# Hoja_Buck2.net
KiCad netlist of a schematic drawn in Altium Designer
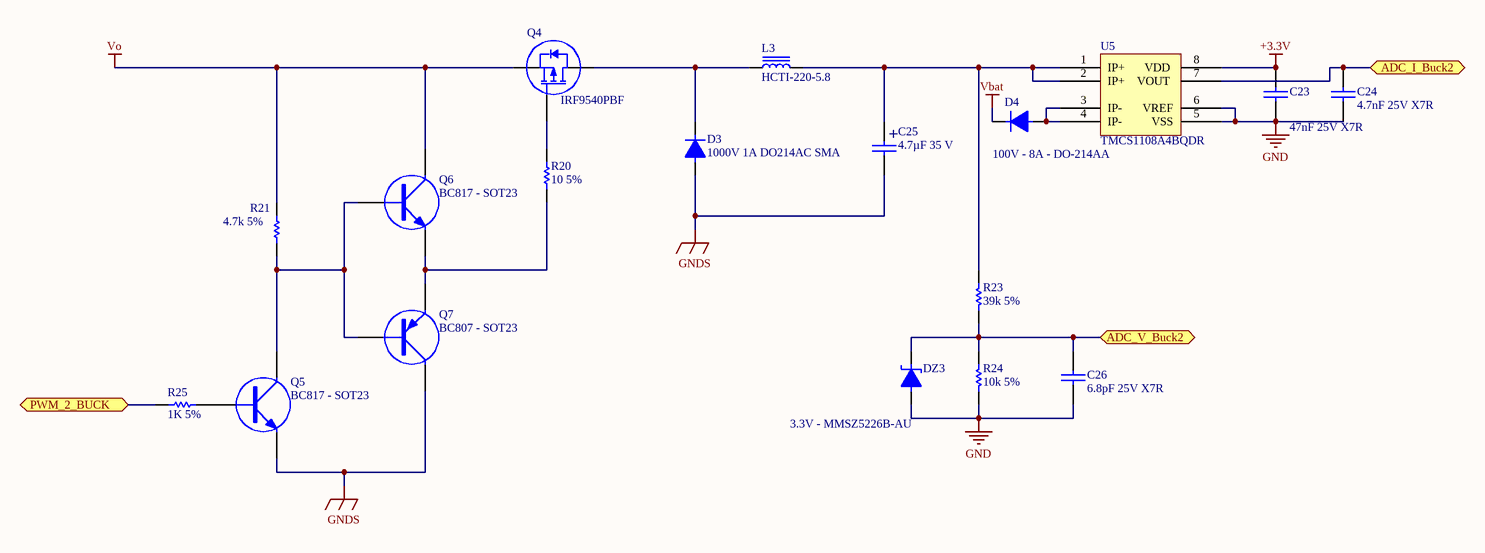
[diagram p0: Hoja_Buck2.SchDoc]

(export (version "E")
  (design (tool "Eeschema 10.0.6"))
  (components
    (comp (ref "C23")
      (value "47nF 25V X7R")
      (footprint "0805")
      (libsource (lib "Libreria_Casera") (part "CAP"))
    )
    (comp (ref "C24")
      (value "4.7nF 25V X7R")
      (footprint "0805")
      (libsource (lib "Libreria_Casera") (part "CAP"))
    )
    (comp (ref "C25")
      (value "4.7µF 35 V")
      (footprint "CAPSMD8x8.3")
      (libsource (lib "Libreria_Casera") (part "CAPPOL"))
    )
    (comp (ref "C26")
      (value "6.8pF 25V X7R")
      (footprint "0805")
      (libsource (lib "Libreria_Casera") (part "CAP"))
    )
    (comp (ref "D3")
      (value "1000V 1A DO214AC SMA")
      (footprint "DO-214AC")
      (description "Diodos Estándar 1000 V 1A Montaje en superficie SMA")
      (libsource (lib "Libreria_Casera") (part "DIODO"))
    )
    (comp (ref "D4")
      (value "100V - 8A - DO-214AA")
      (footprint "SMPA-DIODE")
      (libsource (lib "Libreria_Casera") (part "DIODO"))
    )
    (comp (ref "DZ3")
      (value "3.3V - MMSZ5226B-AU")
      (footprint "sod123")
      (libsource (lib "Libreria_Casera") (part "DIODO ZENER"))
    )
    (comp (ref "L3")
      (value "HCTI-220-5.8")
      (footprint "IND_HCTI-220-5.8:IND_HCTI-220-5.8")
      (description "https://ar.mouser.com/datasheet/2/643/ds-st-high-current-torodial-inductors-series-1661536.pdf")
      (libsource (lib "Libreria_Casera") (part "INDUCTOR"))
    )
    (comp (ref "Q4")
      (value "IRF9540PBF")
      (footprint "TO-220 V")
      (libsource (lib "Libreria_Casera") (part "MOSFET P"))
    )
    (comp (ref "Q5")
      (value "BC817 - SOT23")
      (footprint "SOT23-3")
      (description "45V NPN SMALL SIGNAL TRANSISTOR IN SOT23")
      (libsource (lib "Libreria_Casera") (part "TRANSISTOR NPN"))
    )
    (comp (ref "Q6")
      (value "BC817 - SOT23")
      (footprint "SOT23-3")
      (description "45V NPN SMALL SIGNAL TRANSISTOR IN SOT23")
      (libsource (lib "Libreria_Casera") (part "TRANSISTOR NPN"))
    )
    (comp (ref "Q7")
      (value "BC807 - SOT23")
      (footprint "SOT23-3")
      (libsource (lib "Libreria_Casera") (part "TRANSISTOR PNP"))
    )
    (comp (ref "R20") (value "10 5%") (footprint "0805") (libsource (lib "Libreria_Casera") (part "RES")))
    (comp (ref "R21") (value "4.7k 5%") (footprint "0805") (libsource (lib "Libreria_Casera") (part "RES")))
    (comp (ref "R23") (value "39k 5%") (footprint "0805") (libsource (lib "Libreria_Casera") (part "RES")))
    (comp (ref "R24") (value "10k 5%") (footprint "0805") (libsource (lib "Libreria_Casera") (part "RES")))
    (comp (ref "R25") (value "1K 5%") (footprint "0805") (libsource (lib "Libreria_Casera") (part "RES")))
    (comp (ref "U5")
      (value "TMCS1108A4BQDR")
      (footprint "SOIC8")
      (description "Sensores de corriente 1 canal Efecto Hall Bidireccional 8-SOIC (ancho 0.154\", 3.90mm)")
      (libsource (lib "Libreria_Casera") (part "MLX91221KDC"))
    )
  )
  (nets
    (net (code "1") (name "+3.3V") (class "Default")
      (node (ref "C23") (pin "1") (pinfunction "1_1") (pintype "passive"))
      (node (ref "U5") (pin "8") (pinfunction "VDD_8") (pintype "passive"))
    )
    (net (code "2") (name "/ADC_I_Buck2") (class "Default")
      (node (ref "C24") (pin "1") (pinfunction "1_1") (pintype "passive"))
      (node (ref "U5") (pin "7") (pinfunction "VOUT_7") (pintype "passive"))
    )
    (net (code "3") (name "/ADC_V_Buck2") (class "Default")
      (node (ref "C26") (pin "1") (pinfunction "1_1") (pintype "passive"))
      (node (ref "DZ3") (pin "2") (pinfunction "2_2") (pintype "passive"))
      (node (ref "R23") (pin "1") (pinfunction "1_1") (pintype "passive"))
      (node (ref "R24") (pin "2") (pinfunction "2_2") (pintype "passive"))
    )
    (net (code "4") (name "/PWM_2_BUCK") (class "Default")
      (node (ref "R25") (pin "1") (pinfunction "1_1") (pintype "passive"))
    )
    (net (code "5") (name "GND") (class "Default")
      (node (ref "C23") (pin "2") (pinfunction "2_2") (pintype "passive"))
      (node (ref "C24") (pin "2") (pinfunction "2_2") (pintype "passive"))
      (node (ref "C26") (pin "2") (pinfunction "2_2") (pintype "passive"))
      (node (ref "DZ3") (pin "1") (pinfunction "1_1") (pintype "passive"))
      (node (ref "R24") (pin "1") (pinfunction "1_1") (pintype "passive"))
      (node (ref "U5") (pin "5") (pinfunction "VSS_5") (pintype "passive"))
      (node (ref "U5") (pin "6") (pinfunction "VREF_6") (pintype "passive"))
    )
    (net (code "6") (name "GNDS") (class "Default")
      (node (ref "C25") (pin "2") (pinfunction "2_2") (pintype "passive"))
      (node (ref "D3") (pin "1") (pinfunction "1_1") (pintype "passive"))
      (node (ref "Q5") (pin "3") (pinfunction "E_3") (pintype "passive"))
      (node (ref "Q7") (pin "2") (pinfunction "C_2") (pintype "passive"))
    )
    (net (code "7") (name "Net-(C25-Pad1)") (class "Default")
      (node (ref "C25") (pin "1") (pinfunction "1_1") (pintype "passive"))
      (node (ref "L3") (pin "2") (pinfunction "2_2") (pintype "passive"))
      (node (ref "R23") (pin "2") (pinfunction "2_2") (pintype "passive"))
      (node (ref "U5") (pin "1") (pinfunction "IP+_1") (pintype "passive"))
      (node (ref "U5") (pin "2") (pinfunction "IP+_2") (pintype "passive"))
    )
    (net (code "8") (name "Net-(D4-Pad1)") (class "Default")
      (node (ref "D4") (pin "1") (pinfunction "1_1") (pintype "passive"))
      (node (ref "U5") (pin "3") (pinfunction "IP-_3") (pintype "passive"))
      (node (ref "U5") (pin "4") (pinfunction "IP-_4") (pintype "passive"))
    )
    (net (code "9") (name "Net-(Q4-D)") (class "Default")
      (node (ref "D3") (pin "2") (pinfunction "2_2") (pintype "passive"))
      (node (ref "L3") (pin "1") (pinfunction "1_1") (pintype "passive"))
      (node (ref "Q4") (pin "2") (pinfunction "D_2") (pintype "passive"))
    )
    (net (code "10") (name "Net-(Q4-G)") (class "Default")
      (node (ref "Q4") (pin "1") (pinfunction "G_1") (pintype "passive"))
      (node (ref "R20") (pin "1") (pinfunction "1_1") (pintype "passive"))
    )
    (net (code "11") (name "Net-(Q5-B)") (class "Default")
      (node (ref "Q5") (pin "1") (pinfunction "B_1") (pintype "passive"))
      (node (ref "R25") (pin "2") (pinfunction "2_2") (pintype "passive"))
    )
    (net (code "12") (name "Net-(Q5-C)") (class "Default")
      (node (ref "Q5") (pin "2") (pinfunction "C_2") (pintype "passive"))
      (node (ref "Q6") (pin "1") (pinfunction "B_1") (pintype "passive"))
      (node (ref "Q7") (pin "1") (pinfunction "B_1") (pintype "passive"))
      (node (ref "R21") (pin "2") (pinfunction "2_2") (pintype "passive"))
    )
    (net (code "13") (name "Net-(Q6-E)") (class "Default")
      (node (ref "Q6") (pin "3") (pinfunction "E_3") (pintype "passive"))
      (node (ref "Q7") (pin "3") (pinfunction "E_3") (pintype "passive"))
      (node (ref "R20") (pin "2") (pinfunction "2_2") (pintype "passive"))
    )
    (net (code "14") (name "Vbat") (class "Default")
      (node (ref "D4") (pin "2") (pinfunction "2_2") (pintype "passive"))
    )
    (net (code "15") (name "Vo") (class "Default")
      (node (ref "Q4") (pin "3") (pinfunction "S_3") (pintype "passive"))
      (node (ref "Q6") (pin "2") (pinfunction "C_2") (pintype "passive"))
      (node (ref "R21") (pin "1") (pinfunction "1_1") (pintype "passive"))
    )
  )
)
